# IRLED.net
KiCad netlist of a schematic drawn in Altium Designer
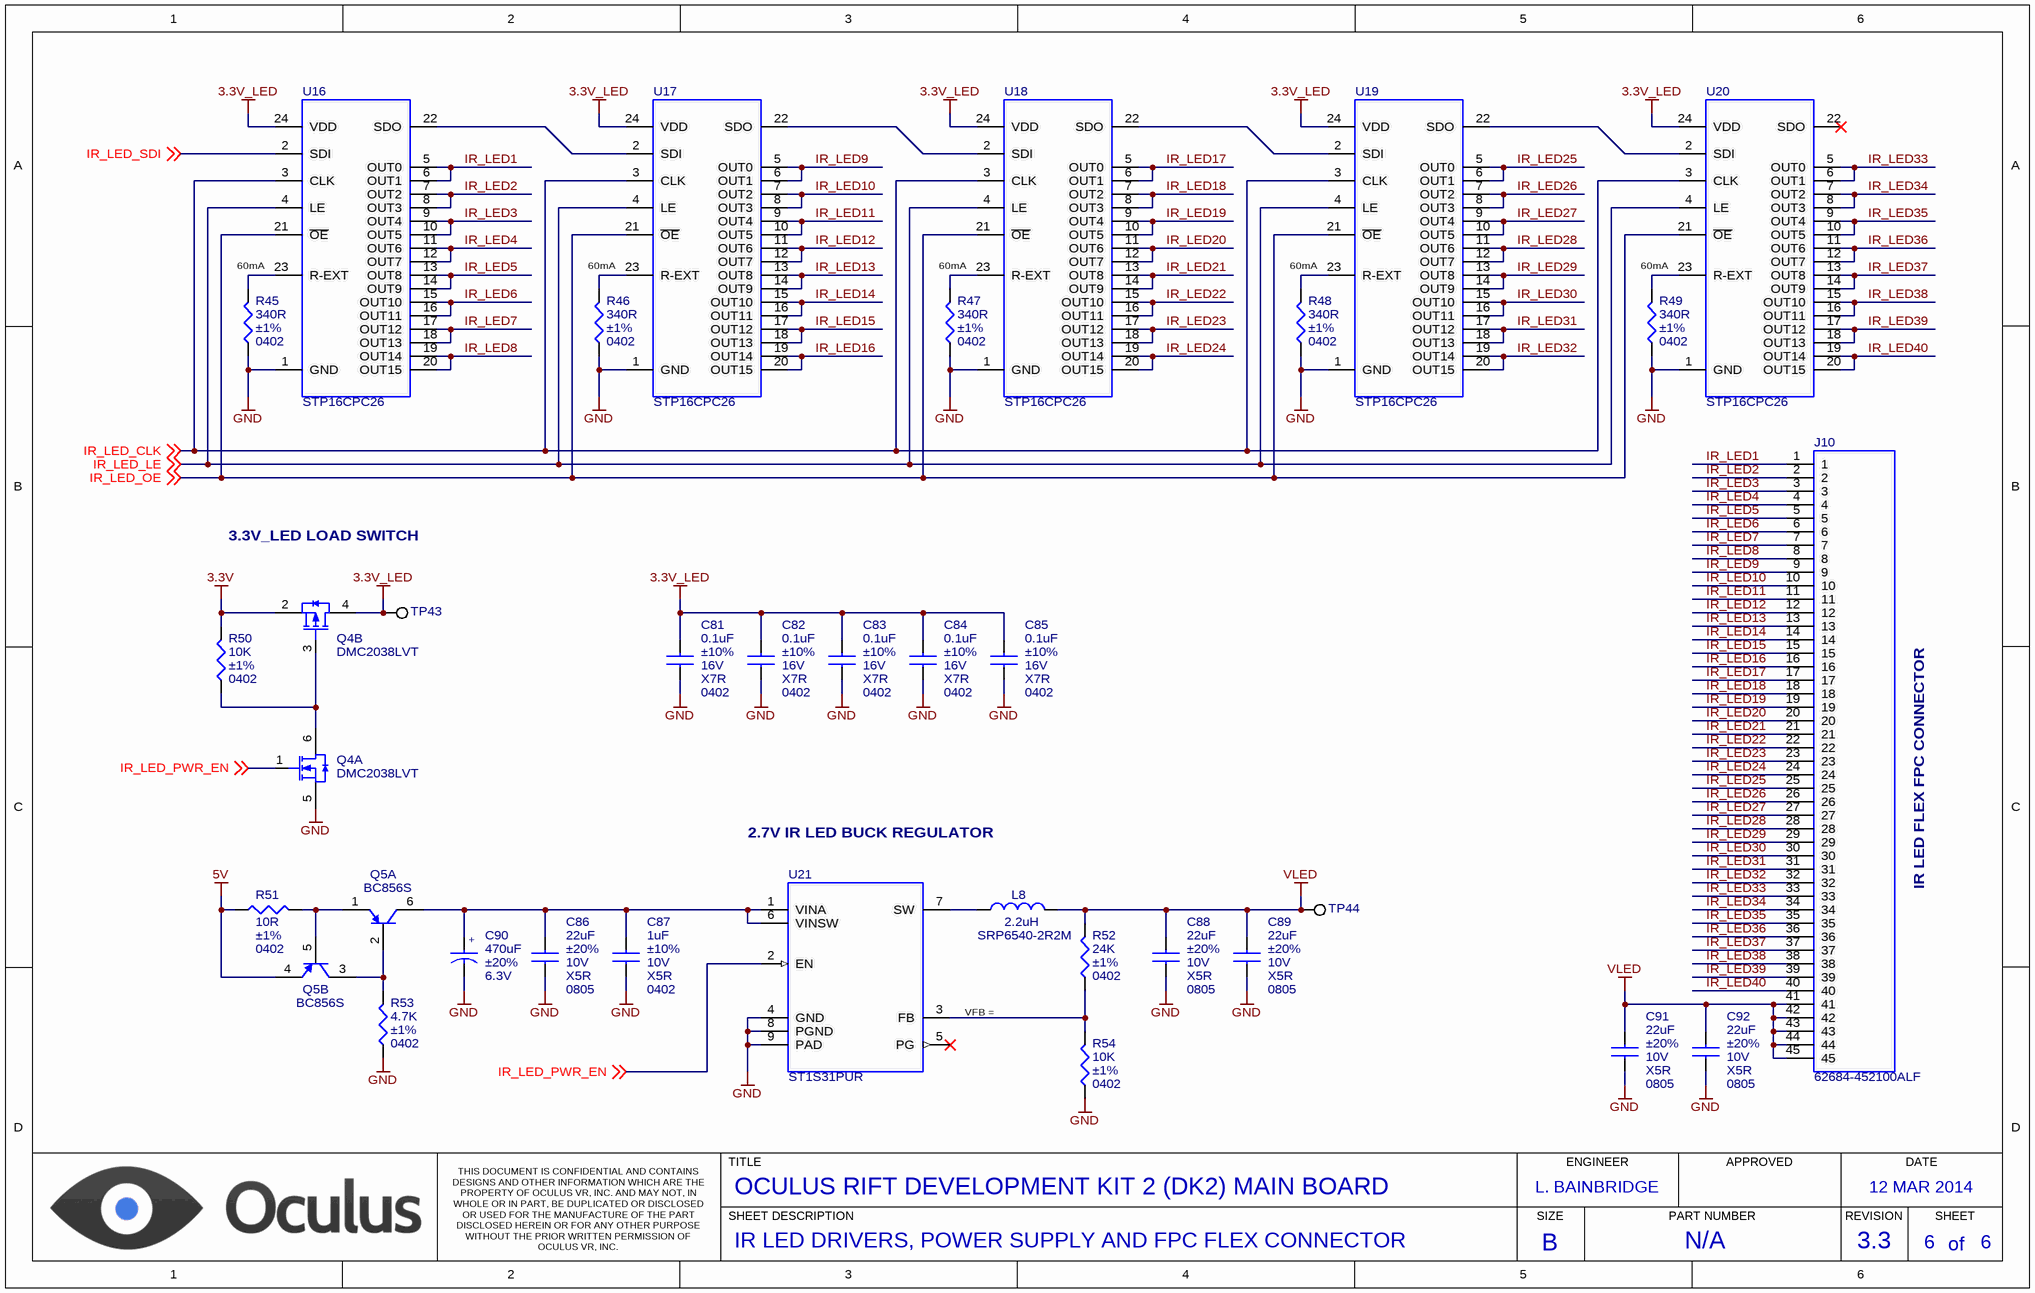
[diagram p0: IRLED.SchDoc]

(export (version "E")
  (design (tool "Eeschema 10.0.6"))
  (components
    (comp (ref "C81")
      (value "0.1uF")
      (footprint "CAP_CERAMIC_0402")
      (description "CAP, CERAMIC, 0.1uF, ±10%, 16V, X7R, 0402")
      (fields
        (field (name "MANUFACTURER") "MURATA ELECTRONICS")
        (field (name "PART NUMBER") "GRM155R71C104KA88D")
        (field (name "TOLERANCE") "±10%")
        (field (name "VOLTAGE") "16V")
        (field (name "DIELECTRIC") "X7R")
        (field (name "PACKAGE") "0402")
      )
      (libsource (lib "DK2") (part "CAP, CERAMIC"))
    )
    (comp (ref "C82")
      (value "0.1uF")
      (footprint "CAP_CERAMIC_0402")
      (description "CAP, CERAMIC, 0.1uF, ±10%, 16V, X7R, 0402")
      (fields
        (field (name "MANUFACTURER") "MURATA ELECTRONICS")
        (field (name "PART NUMBER") "GRM155R71C104KA88D")
        (field (name "TOLERANCE") "±10%")
        (field (name "VOLTAGE") "16V")
        (field (name "DIELECTRIC") "X7R")
        (field (name "PACKAGE") "0402")
      )
      (libsource (lib "DK2") (part "CAP, CERAMIC"))
    )
    (comp (ref "C83")
      (value "0.1uF")
      (footprint "CAP_CERAMIC_0402")
      (description "CAP, CERAMIC, 0.1uF, ±10%, 16V, X7R, 0402")
      (fields
        (field (name "MANUFACTURER") "MURATA ELECTRONICS")
        (field (name "PART NUMBER") "GRM155R71C104KA88D")
        (field (name "TOLERANCE") "±10%")
        (field (name "VOLTAGE") "16V")
        (field (name "DIELECTRIC") "X7R")
        (field (name "PACKAGE") "0402")
      )
      (libsource (lib "DK2") (part "CAP, CERAMIC"))
    )
    (comp (ref "C84")
      (value "0.1uF")
      (footprint "CAP_CERAMIC_0402")
      (description "CAP, CERAMIC, 0.1uF, ±10%, 16V, X7R, 0402")
      (fields
        (field (name "MANUFACTURER") "MURATA ELECTRONICS")
        (field (name "PART NUMBER") "GRM155R71C104KA88D")
        (field (name "TOLERANCE") "±10%")
        (field (name "VOLTAGE") "16V")
        (field (name "DIELECTRIC") "X7R")
        (field (name "PACKAGE") "0402")
      )
      (libsource (lib "DK2") (part "CAP, CERAMIC"))
    )
    (comp (ref "C85")
      (value "0.1uF")
      (footprint "CAP_CERAMIC_0402")
      (description "CAP, CERAMIC, 0.1uF, ±10%, 16V, X7R, 0402")
      (fields
        (field (name "MANUFACTURER") "MURATA ELECTRONICS")
        (field (name "PART NUMBER") "GRM155R71C104KA88D")
        (field (name "TOLERANCE") "±10%")
        (field (name "VOLTAGE") "16V")
        (field (name "DIELECTRIC") "X7R")
        (field (name "PACKAGE") "0402")
      )
      (libsource (lib "DK2") (part "CAP, CERAMIC"))
    )
    (comp (ref "C86")
      (value "22uF")
      (footprint "CAP_CERAMIC_0805")
      (description "CAP, CERAMIC, 22uF, ±20%, 10V, X5R, 0805")
      (fields
        (field (name "MANUFACTURER") "SAMSUNG")
        (field (name "PART NUMBER") "CL21A226MPQNNNE")
        (field (name "TOLERANCE") "±20%")
        (field (name "VOLTAGE") "10V")
        (field (name "DIELECTRIC") "X5R")
        (field (name "PACKAGE") "0805")
      )
      (libsource (lib "DK2") (part "CAP, CERAMIC"))
    )
    (comp (ref "C87")
      (value "1uF")
      (footprint "CAP_CERAMIC_0402")
      (description "CAP, CERAMIC, 1uF, ±10%, 10V, X5R, 0402")
      (fields
        (field (name "MANUFACTURER") "MURATA ELECTRONICS")
        (field (name "PART NUMBER") "GRM155R61A105KE15D")
        (field (name "TOLERANCE") "±10%")
        (field (name "VOLTAGE") "10V")
        (field (name "DIELECTRIC") "X5R")
        (field (name "PACKAGE") "0402")
      )
      (libsource (lib "DK2") (part "CAP, CERAMIC"))
    )
    (comp (ref "C88")
      (value "22uF")
      (footprint "CAP_CERAMIC_0805")
      (description "CAP, CERAMIC, 22uF, ±20%, 10V, X5R, 0805")
      (fields
        (field (name "MANUFACTURER") "SAMSUNG")
        (field (name "PART NUMBER") "CL21A226MPQNNNE")
        (field (name "TOLERANCE") "±20%")
        (field (name "VOLTAGE") "10V")
        (field (name "DIELECTRIC") "X5R")
        (field (name "PACKAGE") "0805")
      )
      (libsource (lib "DK2") (part "CAP, CERAMIC"))
    )
    (comp (ref "C89")
      (value "22uF")
      (footprint "CAP_CERAMIC_0805")
      (description "CAP, CERAMIC, 22uF, ±20%, 10V, X5R, 0805")
      (fields
        (field (name "MANUFACTURER") "SAMSUNG")
        (field (name "PART NUMBER") "CL21A226MPQNNNE")
        (field (name "TOLERANCE") "±20%")
        (field (name "VOLTAGE") "10V")
        (field (name "DIELECTRIC") "X5R")
        (field (name "PACKAGE") "0805")
      )
      (libsource (lib "DK2") (part "CAP, CERAMIC"))
    )
    (comp (ref "C90")
      (value "470uF")
      (footprint "7343-38")
      (description "CAP, TANTALUM, 470uF, ±20%, 6.3V, 7343-38")
      (fields
        (field (name "MANUFACTURER") "PANASONIC")
        (field (name "PART NUMBER") "6TPB470M")
        (field (name "VOLTAGE") "6.3V")
        (field (name "TOLERANCE") "±20%")
      )
      (libsource (lib "DK2") (part "CAP, TANTALUM"))
    )
    (comp (ref "C91")
      (value "22uF")
      (footprint "CAP_CERAMIC_0805")
      (description "CAP, CERAMIC, 22uF, ±20%, 10V, X5R, 0805")
      (fields
        (field (name "MANUFACTURER") "SAMSUNG")
        (field (name "PART NUMBER") "CL21A226MPQNNNE")
        (field (name "TOLERANCE") "±20%")
        (field (name "VOLTAGE") "10V")
        (field (name "DIELECTRIC") "X5R")
        (field (name "PACKAGE") "0805")
      )
      (libsource (lib "DK2") (part "CAP, CERAMIC"))
    )
    (comp (ref "C92")
      (value "22uF")
      (footprint "CAP_CERAMIC_0805")
      (description "CAP, CERAMIC, 22uF, ±20%, 10V, X5R, 0805")
      (fields
        (field (name "MANUFACTURER") "SAMSUNG")
        (field (name "PART NUMBER") "CL21A226MPQNNNE")
        (field (name "TOLERANCE") "±20%")
        (field (name "VOLTAGE") "10V")
        (field (name "DIELECTRIC") "X5R")
        (field (name "PACKAGE") "0805")
      )
      (libsource (lib "DK2") (part "CAP, CERAMIC"))
    )
    (comp (ref "J10")
      (value "62684-452100ALF")
      (footprint "FCI_62684-452100ALF")
      (description "CONNECTOR, FPC HEADER, 45 POS, 0.5MM PITCH")
      (fields (field (name "MANUFACTURER") "FCI"))
      (libsource (lib "DK2") (part "62684-452100ALF"))
    )
    (comp (ref "L8")
      (value "2.2uH")
      (footprint "SRP6540")
      (description "INDUCTOR, SHIELDED POWER, 2.2uH, 9A")
      (fields (field (name "MANUFACTURER") "BOURNES") (field (name "PART NUMBER") "SRP6540-2R2M"))
      (libsource (lib "DK2") (part "INDUCTOR"))
    )
    (comp (ref "Q4")
      (value "DMC2038LVT")
      (footprint "TSOT26")
      (description "FET, COMPLEMENTARY, LOGIC LEVEL")
      (fields (field (name "MANUFACTURER") "DIODES INC"))
      (libsource (lib "DK2") (part "DMC2038LVT"))
    )
    (comp (ref "Q5")
      (value "BC856S")
      (footprint "SOT363")
      (description "TRANSISTOR, DUAL SILICON PNP")
      (fields (field (name "MANUFACTURER") "INFINEON") (field (name "PART NUMBER") "BC856S H6327"))
      (libsource (lib "DK2") (part "BC856S"))
    )
    (comp (ref "R45")
      (value "340R")
      (footprint "RESISTOR_0402")
      (description "RES 340 OHM, 1/10W, ±1%, 0402")
      (fields
        (field (name "MANUFACTURER") "PANASONIC")
        (field (name "PART NUMBER") "ERJ-2RKF3400X")
        (field (name "PACKAGE") "0402")
        (field (name "TOLERANCE") "±1%")
      )
      (libsource (lib "DK2") (part "RESISTOR"))
    )
    (comp (ref "R46")
      (value "340R")
      (footprint "RESISTOR_0402")
      (description "RES 340 OHM, 1/10W, ±1%, 0402")
      (fields
        (field (name "MANUFACTURER") "PANASONIC")
        (field (name "PART NUMBER") "ERJ-2RKF3400X")
        (field (name "PACKAGE") "0402")
        (field (name "TOLERANCE") "±1%")
      )
      (libsource (lib "DK2") (part "RESISTOR"))
    )
    (comp (ref "R47")
      (value "340R")
      (footprint "RESISTOR_0402")
      (description "RES 340 OHM, 1/10W, ±1%, 0402")
      (fields
        (field (name "MANUFACTURER") "PANASONIC")
        (field (name "PART NUMBER") "ERJ-2RKF3400X")
        (field (name "PACKAGE") "0402")
        (field (name "TOLERANCE") "±1%")
      )
      (libsource (lib "DK2") (part "RESISTOR"))
    )
    (comp (ref "R48")
      (value "340R")
      (footprint "RESISTOR_0402")
      (description "RES 340 OHM, 1/10W, ±1%, 0402")
      (fields
        (field (name "MANUFACTURER") "PANASONIC")
        (field (name "PART NUMBER") "ERJ-2RKF3400X")
        (field (name "PACKAGE") "0402")
        (field (name "TOLERANCE") "±1%")
      )
      (libsource (lib "DK2") (part "RESISTOR"))
    )
    (comp (ref "R49")
      (value "340R")
      (footprint "RESISTOR_0402")
      (description "RES 340 OHM, 1/10W, ±1%, 0402")
      (fields
        (field (name "MANUFACTURER") "PANASONIC")
        (field (name "PART NUMBER") "ERJ-2RKF3400X")
        (field (name "PACKAGE") "0402")
        (field (name "TOLERANCE") "±1%")
      )
      (libsource (lib "DK2") (part "RESISTOR"))
    )
    (comp (ref "R50")
      (value "10K")
      (footprint "RESISTOR_0402")
      (description "RES, 10K OHM, 1/10W, ±1%, 0402")
      (fields
        (field (name "MANUFACTURER") "PANASONIC")
        (field (name "PART NUMBER") "ERJ-2RKF1002X")
        (field (name "PACKAGE") "0402")
        (field (name "TOLERANCE") "±1%")
      )
      (libsource (lib "DK2") (part "RESISTOR"))
    )
    (comp (ref "R51")
      (value "10R")
      (footprint "RESISTOR_0402")
      (description "RES, 10 OHM, 1/10W, ±1%, 0402")
      (fields
        (field (name "MANUFACTURER") "PANASONIC")
        (field (name "PART NUMBER") "ERJ-2RKF10R0X")
        (field (name "PACKAGE") "0402")
        (field (name "TOLERANCE") "±1%")
      )
      (libsource (lib "DK2") (part "RESISTOR"))
    )
    (comp (ref "R52")
      (value "24K")
      (footprint "RESISTOR_0402")
      (description "RES, 24K OHM, 1/10W, ±1%, 0402")
      (fields
        (field (name "MANUFACTURER") "PANASONIC")
        (field (name "PART NUMBER") "ERJ-2RKF2402X")
        (field (name "PACKAGE") "0402")
        (field (name "TOLERANCE") "±1%")
      )
      (libsource (lib "DK2") (part "RESISTOR"))
    )
    (comp (ref "R53")
      (value "4.7K")
      (footprint "RESISTOR_0402")
      (description "RES, 4.7K OHM, 1/10W, ±1%, 0402")
      (fields
        (field (name "MANUFACTURER") "PANASONIC")
        (field (name "PART NUMBER") "ERJ-2RKF4701X")
        (field (name "PACKAGE") "0402")
        (field (name "TOLERANCE") "±1%")
      )
      (libsource (lib "DK2") (part "RESISTOR"))
    )
    (comp (ref "R54")
      (value "10K")
      (footprint "RESISTOR_0402")
      (description "RES, 10K OHM, 1/10W, ±1%, 0402")
      (fields
        (field (name "MANUFACTURER") "PANASONIC")
        (field (name "PART NUMBER") "ERJ-2RKF1002X")
        (field (name "PACKAGE") "0402")
        (field (name "TOLERANCE") "±1%")
      )
      (libsource (lib "DK2") (part "RESISTOR"))
    )
    (comp (ref "TP43")
      (value "TEST POINT")
      (footprint "TEST_POINT_PAD_1MM")
      (libsource (lib "DK2") (part "TEST_POINT_GENERIC"))
    )
    (comp (ref "TP44")
      (value "TEST POINT")
      (footprint "TEST_POINT_PAD_1MM")
      (libsource (lib "DK2") (part "TEST_POINT_GENERIC"))
    )
    (comp (ref "U16")
      (value "STP16CPC26")
      (footprint "TSSOP24")
      (description "IC, LED DRIVER, 16-BIT CONSTANT CURRENT SINK DRIVER")
      (fields (field (name "MANUFACTURER") "STMICROELECTRONICS") (field (name "PART NUMBER") "STP16CPC26TTR"))
      (libsource (lib "DK2") (part "STP16CPC26"))
    )
    (comp (ref "U17")
      (value "STP16CPC26")
      (footprint "TSSOP24")
      (description "IC, LED DRIVER, 16-BIT CONSTANT CURRENT SINK DRIVER")
      (fields (field (name "MANUFACTURER") "STMICROELECTRONICS") (field (name "PART NUMBER") "STP16CPC26TTR"))
      (libsource (lib "DK2") (part "STP16CPC26"))
    )
    (comp (ref "U18")
      (value "STP16CPC26")
      (footprint "TSSOP24")
      (description "IC, LED DRIVER, 16-BIT CONSTANT CURRENT SINK DRIVER")
      (fields (field (name "MANUFACTURER") "STMICROELECTRONICS") (field (name "PART NUMBER") "STP16CPC26TTR"))
      (libsource (lib "DK2") (part "STP16CPC26"))
    )
    (comp (ref "U19")
      (value "STP16CPC26")
      (footprint "TSSOP24")
      (description "IC, LED DRIVER, 16-BIT CONSTANT CURRENT SINK DRIVER")
      (fields (field (name "MANUFACTURER") "STMICROELECTRONICS") (field (name "PART NUMBER") "STP16CPC26TTR"))
      (libsource (lib "DK2") (part "STP16CPC26"))
    )
    (comp (ref "U20")
      (value "STP16CPC26")
      (footprint "TSSOP24")
      (description "IC, LED DRIVER, 16-BIT CONSTANT CURRENT SINK DRIVER")
      (fields (field (name "MANUFACTURER") "STMICROELECTRONICS") (field (name "PART NUMBER") "STP16CPC26TTR"))
      (libsource (lib "DK2") (part "STP16CPC26"))
    )
    (comp (ref "U21")
      (value "ST1S31PUR")
      (footprint "VFDFPN-3x3-8L")
      (description "IC, BUCK REGULATOR, 3A")
      (fields (field (name "MANUFACTURER") "STMICROELECTRONICS"))
      (libsource (lib "DK2") (part "ST1S31PUR"))
    )
  )
  (nets
    (net (code "1") (name "/IR_LED1") (class "Default")
      (node (ref "J10") (pin "1") (pinfunction "1_1") (pintype "passive"))
      (node (ref "U16") (pin "5") (pinfunction "OUT0_5") (pintype "passive"))
      (node (ref "U16") (pin "6") (pinfunction "OUT1_6") (pintype "passive"))
    )
    (net (code "2") (name "/IR_LED2") (class "Default")
      (node (ref "J10") (pin "2") (pinfunction "2_2") (pintype "passive"))
      (node (ref "U16") (pin "7") (pinfunction "OUT2_7") (pintype "passive"))
      (node (ref "U16") (pin "8") (pinfunction "OUT3_8") (pintype "passive"))
    )
    (net (code "3") (name "/IR_LED3") (class "Default")
      (node (ref "J10") (pin "3") (pinfunction "3_3") (pintype "passive"))
      (node (ref "U16") (pin "10") (pinfunction "OUT5_10") (pintype "passive"))
      (node (ref "U16") (pin "9") (pinfunction "OUT4_9") (pintype "passive"))
    )
    (net (code "4") (name "/IR_LED4") (class "Default")
      (node (ref "J10") (pin "4") (pinfunction "4_4") (pintype "passive"))
      (node (ref "U16") (pin "11") (pinfunction "OUT6_11") (pintype "passive"))
      (node (ref "U16") (pin "12") (pinfunction "OUT7_12") (pintype "passive"))
    )
    (net (code "5") (name "/IR_LED5") (class "Default")
      (node (ref "J10") (pin "5") (pinfunction "5_5") (pintype "passive"))
      (node (ref "U16") (pin "13") (pinfunction "OUT8_13") (pintype "passive"))
      (node (ref "U16") (pin "14") (pinfunction "OUT9_14") (pintype "passive"))
    )
    (net (code "6") (name "/IR_LED6") (class "Default")
      (node (ref "J10") (pin "6") (pinfunction "6_6") (pintype "passive"))
      (node (ref "U16") (pin "15") (pinfunction "OUT10_15") (pintype "passive"))
      (node (ref "U16") (pin "16") (pinfunction "OUT11_16") (pintype "passive"))
    )
    (net (code "7") (name "/IR_LED7") (class "Default")
      (node (ref "J10") (pin "7") (pinfunction "7_7") (pintype "passive"))
      (node (ref "U16") (pin "17") (pinfunction "OUT12_17") (pintype "passive"))
      (node (ref "U16") (pin "18") (pinfunction "OUT13_18") (pintype "passive"))
    )
    (net (code "8") (name "/IR_LED8") (class "Default")
      (node (ref "J10") (pin "8") (pinfunction "8_8") (pintype "passive"))
      (node (ref "U16") (pin "19") (pinfunction "OUT14_19") (pintype "passive"))
      (node (ref "U16") (pin "20") (pinfunction "OUT15_20") (pintype "passive"))
    )
    (net (code "9") (name "/IR_LED9") (class "Default")
      (node (ref "J10") (pin "9") (pinfunction "9_9") (pintype "passive"))
      (node (ref "U17") (pin "5") (pinfunction "OUT0_5") (pintype "passive"))
      (node (ref "U17") (pin "6") (pinfunction "OUT1_6") (pintype "passive"))
    )
    (net (code "10") (name "/IR_LED10") (class "Default")
      (node (ref "J10") (pin "10") (pinfunction "10_10") (pintype "passive"))
      (node (ref "U17") (pin "7") (pinfunction "OUT2_7") (pintype "passive"))
      (node (ref "U17") (pin "8") (pinfunction "OUT3_8") (pintype "passive"))
    )
    (net (code "11") (name "/IR_LED11") (class "Default")
      (node (ref "J10") (pin "11") (pinfunction "11_11") (pintype "passive"))
      (node (ref "U17") (pin "10") (pinfunction "OUT5_10") (pintype "passive"))
      (node (ref "U17") (pin "9") (pinfunction "OUT4_9") (pintype "passive"))
    )
    (net (code "12") (name "/IR_LED12") (class "Default")
      (node (ref "J10") (pin "12") (pinfunction "12_12") (pintype "passive"))
      (node (ref "U17") (pin "11") (pinfunction "OUT6_11") (pintype "passive"))
      (node (ref "U17") (pin "12") (pinfunction "OUT7_12") (pintype "passive"))
    )
    (net (code "13") (name "/IR_LED13") (class "Default")
      (node (ref "J10") (pin "13") (pinfunction "13_13") (pintype "passive"))
      (node (ref "U17") (pin "13") (pinfunction "OUT8_13") (pintype "passive"))
      (node (ref "U17") (pin "14") (pinfunction "OUT9_14") (pintype "passive"))
    )
    (net (code "14") (name "/IR_LED14") (class "Default")
      (node (ref "J10") (pin "14") (pinfunction "14_14") (pintype "passive"))
      (node (ref "U17") (pin "15") (pinfunction "OUT10_15") (pintype "passive"))
      (node (ref "U17") (pin "16") (pinfunction "OUT11_16") (pintype "passive"))
    )
    (net (code "15") (name "/IR_LED15") (class "Default")
      (node (ref "J10") (pin "15") (pinfunction "15_15") (pintype "passive"))
      (node (ref "U17") (pin "17") (pinfunction "OUT12_17") (pintype "passive"))
      (node (ref "U17") (pin "18") (pinfunction "OUT13_18") (pintype "passive"))
    )
    (net (code "16") (name "/IR_LED16") (class "Default")
      (node (ref "J10") (pin "16") (pinfunction "16_16") (pintype "passive"))
      (node (ref "U17") (pin "19") (pinfunction "OUT14_19") (pintype "passive"))
      (node (ref "U17") (pin "20") (pinfunction "OUT15_20") (pintype "passive"))
    )
    (net (code "17") (name "/IR_LED17") (class "Default")
      (node (ref "J10") (pin "17") (pinfunction "17_17") (pintype "passive"))
      (node (ref "U18") (pin "5") (pinfunction "OUT0_5") (pintype "passive"))
      (node (ref "U18") (pin "6") (pinfunction "OUT1_6") (pintype "passive"))
    )
    (net (code "18") (name "/IR_LED18") (class "Default")
      (node (ref "J10") (pin "18") (pinfunction "18_18") (pintype "passive"))
      (node (ref "U18") (pin "7") (pinfunction "OUT2_7") (pintype "passive"))
      (node (ref "U18") (pin "8") (pinfunction "OUT3_8") (pintype "passive"))
    )
    (net (code "19") (name "/IR_LED19") (class "Default")
      (node (ref "J10") (pin "19") (pinfunction "19_19") (pintype "passive"))
      (node (ref "U18") (pin "10") (pinfunction "OUT5_10") (pintype "passive"))
      (node (ref "U18") (pin "9") (pinfunction "OUT4_9") (pintype "passive"))
    )
    (net (code "20") (name "/IR_LED20") (class "Default")
      (node (ref "J10") (pin "20") (pinfunction "20_20") (pintype "passive"))
      (node (ref "U18") (pin "11") (pinfunction "OUT6_11") (pintype "passive"))
      (node (ref "U18") (pin "12") (pinfunction "OUT7_12") (pintype "passive"))
    )
    (net (code "21") (name "/IR_LED21") (class "Default")
      (node (ref "J10") (pin "21") (pinfunction "21_21") (pintype "passive"))
      (node (ref "U18") (pin "13") (pinfunction "OUT8_13") (pintype "passive"))
      (node (ref "U18") (pin "14") (pinfunction "OUT9_14") (pintype "passive"))
    )
    (net (code "22") (name "/IR_LED22") (class "Default")
      (node (ref "J10") (pin "22") (pinfunction "22_22") (pintype "passive"))
      (node (ref "U18") (pin "15") (pinfunction "OUT10_15") (pintype "passive"))
      (node (ref "U18") (pin "16") (pinfunction "OUT11_16") (pintype "passive"))
    )
    (net (code "23") (name "/IR_LED23") (class "Default")
      (node (ref "J10") (pin "23") (pinfunction "23_23") (pintype "passive"))
      (node (ref "U18") (pin "17") (pinfunction "OUT12_17") (pintype "passive"))
      (node (ref "U18") (pin "18") (pinfunction "OUT13_18") (pintype "passive"))
    )
    (net (code "24") (name "/IR_LED24") (class "Default")
      (node (ref "J10") (pin "24") (pinfunction "24_24") (pintype "passive"))
      (node (ref "U18") (pin "19") (pinfunction "OUT14_19") (pintype "passive"))
      (node (ref "U18") (pin "20") (pinfunction "OUT15_20") (pintype "passive"))
    )
    (net (code "25") (name "/IR_LED25") (class "Default")
      (node (ref "J10") (pin "25") (pinfunction "25_25") (pintype "passive"))
      (node (ref "U19") (pin "5") (pinfunction "OUT0_5") (pintype "passive"))
      (node (ref "U19") (pin "6") (pinfunction "OUT1_6") (pintype "passive"))
    )
    (net (code "26") (name "/IR_LED26") (class "Default")
      (node (ref "J10") (pin "26") (pinfunction "26_26") (pintype "passive"))
      (node (ref "U19") (pin "7") (pinfunction "OUT2_7") (pintype "passive"))
      (node (ref "U19") (pin "8") (pinfunction "OUT3_8") (pintype "passive"))
    )
    (net (code "27") (name "/IR_LED27") (class "Default")
      (node (ref "J10") (pin "27") (pinfunction "27_27") (pintype "passive"))
      (node (ref "U19") (pin "10") (pinfunction "OUT5_10") (pintype "passive"))
      (node (ref "U19") (pin "9") (pinfunction "OUT4_9") (pintype "passive"))
    )
    (net (code "28") (name "/IR_LED28") (class "Default")
      (node (ref "J10") (pin "28") (pinfunction "28_28") (pintype "passive"))
      (node (ref "U19") (pin "11") (pinfunction "OUT6_11") (pintype "passive"))
      (node (ref "U19") (pin "12") (pinfunction "OUT7_12") (pintype "passive"))
    )
    (net (code "29") (name "/IR_LED29") (class "Default")
      (node (ref "J10") (pin "29") (pinfunction "29_29") (pintype "passive"))
      (node (ref "U19") (pin "13") (pinfunction "OUT8_13") (pintype "passive"))
      (node (ref "U19") (pin "14") (pinfunction "OUT9_14") (pintype "passive"))
    )
    (net (code "30") (name "/IR_LED30") (class "Default")
      (node (ref "J10") (pin "30") (pinfunction "30_30") (pintype "passive"))
      (node (ref "U19") (pin "15") (pinfunction "OUT10_15") (pintype "passive"))
      (node (ref "U19") (pin "16") (pinfunction "OUT11_16") (pintype "passive"))
    )
    (net (code "31") (name "/IR_LED31") (class "Default")
      (node (ref "J10") (pin "31") (pinfunction "31_31") (pintype "passive"))
      (node (ref "U19") (pin "17") (pinfunction "OUT12_17") (pintype "passive"))
      (node (ref "U19") (pin "18") (pinfunction "OUT13_18") (pintype "passive"))
    )
    (net (code "32") (name "/IR_LED32") (class "Default")
      (node (ref "J10") (pin "32") (pinfunction "32_32") (pintype "passive"))
      (node (ref "U19") (pin "19") (pinfunction "OUT14_19") (pintype "passive"))
      (node (ref "U19") (pin "20") (pinfunction "OUT15_20") (pintype "passive"))
    )
    (net (code "33") (name "/IR_LED33") (class "Default")
      (node (ref "J10") (pin "33") (pinfunction "33_33") (pintype "passive"))
      (node (ref "U20") (pin "5") (pinfunction "OUT0_5") (pintype "passive"))
      (node (ref "U20") (pin "6") (pinfunction "OUT1_6") (pintype "passive"))
    )
    (net (code "34") (name "/IR_LED34") (class "Default")
      (node (ref "J10") (pin "34") (pinfunction "34_34") (pintype "passive"))
      (node (ref "U20") (pin "7") (pinfunction "OUT2_7") (pintype "passive"))
      (node (ref "U20") (pin "8") (pinfunction "OUT3_8") (pintype "passive"))
    )
    (net (code "35") (name "/IR_LED35") (class "Default")
      (node (ref "J10") (pin "35") (pinfunction "35_35") (pintype "passive"))
      (node (ref "U20") (pin "10") (pinfunction "OUT5_10") (pintype "passive"))
      (node (ref "U20") (pin "9") (pinfunction "OUT4_9") (pintype "passive"))
    )
    (net (code "36") (name "/IR_LED36") (class "Default")
      (node (ref "J10") (pin "36") (pinfunction "36_36") (pintype "passive"))
      (node (ref "U20") (pin "11") (pinfunction "OUT6_11") (pintype "passive"))
      (node (ref "U20") (pin "12") (pinfunction "OUT7_12") (pintype "passive"))
    )
    (net (code "37") (name "/IR_LED37") (class "Default")
      (node (ref "J10") (pin "37") (pinfunction "37_37") (pintype "passive"))
      (node (ref "U20") (pin "13") (pinfunction "OUT8_13") (pintype "passive"))
      (node (ref "U20") (pin "14") (pinfunction "OUT9_14") (pintype "passive"))
    )
    (net (code "38") (name "/IR_LED38") (class "Default")
      (node (ref "J10") (pin "38") (pinfunction "38_38") (pintype "passive"))
      (node (ref "U20") (pin "15") (pinfunction "OUT10_15") (pintype "passive"))
      (node (ref "U20") (pin "16") (pinfunction "OUT11_16") (pintype "passive"))
    )
    (net (code "39") (name "/IR_LED39") (class "Default")
      (node (ref "J10") (pin "39") (pinfunction "39_39") (pintype "passive"))
      (node (ref "U20") (pin "17") (pinfunction "OUT12_17") (pintype "passive"))
      (node (ref "U20") (pin "18") (pinfunction "OUT13_18") (pintype "passive"))
    )
    (net (code "40") (name "/IR_LED40") (class "Default")
      (node (ref "J10") (pin "40") (pinfunction "40_40") (pintype "passive"))
      (node (ref "U20") (pin "19") (pinfunction "OUT14_19") (pintype "passive"))
      (node (ref "U20") (pin "20") (pinfunction "OUT15_20") (pintype "passive"))
    )
    (net (code "41") (name "3.3V") (class "Default")
      (node (ref "Q4") (pin "2") (pinfunction "S_2") (pintype "passive"))
      (node (ref "R50") (pin "2") (pinfunction "2_2") (pintype "passive"))
    )
    (net (code "42") (name "3.3V_LED") (class "Default")
      (node (ref "C81") (pin "1") (pinfunction "1_1") (pintype "passive"))
      (node (ref "C82") (pin "1") (pinfunction "1_1") (pintype "passive"))
      (node (ref "C83") (pin "1") (pinfunction "1_1") (pintype "passive"))
      (node (ref "C84") (pin "1") (pinfunction "1_1") (pintype "passive"))
      (node (ref "C85") (pin "1") (pinfunction "1_1") (pintype "passive"))
      (node (ref "Q4") (pin "4") (pinfunction "D_4") (pintype "passive"))
      (node (ref "TP43") (pin "1") (pinfunction "1_1") (pintype "passive"))
      (node (ref "U16") (pin "24") (pinfunction "VDD_24") (pintype "passive"))
      (node (ref "U17") (pin "24") (pinfunction "VDD_24") (pintype "passive"))
      (node (ref "U18") (pin "24") (pinfunction "VDD_24") (pintype "passive"))
      (node (ref "U19") (pin "24") (pinfunction "VDD_24") (pintype "passive"))
      (node (ref "U20") (pin "24") (pinfunction "VDD_24") (pintype "passive"))
    )
    (net (code "43") (name "5V") (class "Default")
      (node (ref "Q5") (pin "4") (pinfunction "E_4") (pintype "passive"))
      (node (ref "R51") (pin "1") (pinfunction "1_1") (pintype "passive"))
    )
    (net (code "44") (name "GND") (class "Default")
      (node (ref "C81") (pin "2") (pinfunction "2_2") (pintype "passive"))
      (node (ref "C82") (pin "2") (pinfunction "2_2") (pintype "passive"))
      (node (ref "C83") (pin "2") (pinfunction "2_2") (pintype "passive"))
      (node (ref "C84") (pin "2") (pinfunction "2_2") (pintype "passive"))
      (node (ref "C85") (pin "2") (pinfunction "2_2") (pintype "passive"))
      (node (ref "C86") (pin "2") (pinfunction "2_2") (pintype "passive"))
      (node (ref "C87") (pin "2") (pinfunction "2_2") (pintype "passive"))
      (node (ref "C88") (pin "2") (pinfunction "2_2") (pintype "passive"))
      (node (ref "C89") (pin "2") (pinfunction "2_2") (pintype "passive"))
      (node (ref "C90") (pin "2") (pinfunction "2_2") (pintype "passive"))
      (node (ref "C91") (pin "2") (pinfunction "2_2") (pintype "passive"))
      (node (ref "C92") (pin "2") (pinfunction "2_2") (pintype "passive"))
      (node (ref "Q4") (pin "5") (pinfunction "S_5") (pintype "passive"))
      (node (ref "R45") (pin "1") (pinfunction "1_1") (pintype "passive"))
      (node (ref "R46") (pin "1") (pinfunction "1_1") (pintype "passive"))
      (node (ref "R47") (pin "1") (pinfunction "1_1") (pintype "passive"))
      (node (ref "R48") (pin "1") (pinfunction "1_1") (pintype "passive"))
      (node (ref "R49") (pin "1") (pinfunction "1_1") (pintype "passive"))
      (node (ref "R53") (pin "1") (pinfunction "1_1") (pintype "passive"))
      (node (ref "R54") (pin "1") (pinfunction "1_1") (pintype "passive"))
      (node (ref "U16") (pin "1") (pinfunction "GND_1") (pintype "passive"))
      (node (ref "U17") (pin "1") (pinfunction "GND_1") (pintype "passive"))
      (node (ref "U18") (pin "1") (pinfunction "GND_1") (pintype "passive"))
      (node (ref "U19") (pin "1") (pinfunction "GND_1") (pintype "passive"))
      (node (ref "U20") (pin "1") (pinfunction "GND_1") (pintype "passive"))
      (node (ref "U21") (pin "4") (pinfunction "GND_4") (pintype "power_in"))
      (node (ref "U21") (pin "8") (pinfunction "PGND_8") (pintype "power_in"))
      (node (ref "U21") (pin "9") (pinfunction "PAD_9") (pintype "passive"))
    )
    (net (code "45") (name "IR_LED_CLK") (class "Default")
      (node (ref "U16") (pin "3") (pinfunction "CLK_3") (pintype "passive"))
      (node (ref "U17") (pin "3") (pinfunction "CLK_3") (pintype "passive"))
      (node (ref "U18") (pin "3") (pinfunction "CLK_3") (pintype "passive"))
      (node (ref "U19") (pin "3") (pinfunction "CLK_3") (pintype "passive"))
      (node (ref "U20") (pin "3") (pinfunction "CLK_3") (pintype "passive"))
    )
    (net (code "46") (name "IR_LED_LE") (class "Default")
      (node (ref "U16") (pin "4") (pinfunction "LE_4") (pintype "passive"))
      (node (ref "U17") (pin "4") (pinfunction "LE_4") (pintype "passive"))
      (node (ref "U18") (pin "4") (pinfunction "LE_4") (pintype "passive"))
      (node (ref "U19") (pin "4") (pinfunction "LE_4") (pintype "passive"))
      (node (ref "U20") (pin "4") (pinfunction "LE_4") (pintype "passive"))
    )
    (net (code "47") (name "IR_LED_OE") (class "Default")
      (node (ref "U16") (pin "21") (pinfunction "~{OE}_21") (pintype "passive"))
      (node (ref "U17") (pin "21") (pinfunction "~{OE}_21") (pintype "passive"))
      (node (ref "U18") (pin "21") (pinfunction "~{OE}_21") (pintype "passive"))
      (node (ref "U19") (pin "21") (pinfunction "~{OE}_21") (pintype "passive"))
      (node (ref "U20") (pin "21") (pinfunction "~{OE}_21") (pintype "passive"))
    )
    (net (code "48") (name "IR_LED_PWR_EN") (class "Default")
      (node (ref "Q4") (pin "1") (pinfunction "G_1") (pintype "passive"))
      (node (ref "U21") (pin "2") (pinfunction "EN_2") (pintype "input"))
    )
    (net (code "49") (name "IR_LED_SDI") (class "Default")
      (node (ref "U16") (pin "2") (pinfunction "SDI_2") (pintype "passive"))
    )
    (net (code "50") (name "Net-(Q4A-D)") (class "Default")
      (node (ref "Q4") (pin "3") (pinfunction "G_3") (pintype "passive"))
      (node (ref "Q4") (pin "6") (pinfunction "D_6") (pintype "passive"))
      (node (ref "R50") (pin "1") (pinfunction "1_1") (pintype "passive"))
    )
    (net (code "51") (name "Net-(Q5A-B)") (class "Default")
      (node (ref "Q5") (pin "2") (pinfunction "B_2") (pintype "passive"))
      (node (ref "Q5") (pin "3") (pinfunction "C_3") (pintype "passive"))
      (node (ref "R53") (pin "2") (pinfunction "2_2") (pintype "passive"))
    )
    (net (code "52") (name "Net-(Q5A-C)") (class "Default")
      (node (ref "C86") (pin "1") (pinfunction "1_1") (pintype "passive"))
      (node (ref "C87") (pin "1") (pinfunction "1_1") (pintype "passive"))
      (node (ref "C90") (pin "1") (pinfunction "1_1") (pintype "passive"))
      (node (ref "Q5") (pin "6") (pinfunction "C_6") (pintype "passive"))
      (node (ref "U21") (pin "1") (pinfunction "VINA_1") (pintype "power_in"))
      (node (ref "U21") (pin "6") (pinfunction "VINSW_6") (pintype "power_in"))
    )
    (net (code "53") (name "Net-(Q5A-E)") (class "Default")
      (node (ref "Q5") (pin "1") (pinfunction "E_1") (pintype "passive"))
      (node (ref "Q5") (pin "5") (pinfunction "B_5") (pintype "passive"))
      (node (ref "R51") (pin "2") (pinfunction "2_2") (pintype "passive"))
    )
    (net (code "54") (name "Net-(U16-R-EXT)") (class "Default")
      (node (ref "R45") (pin "2") (pinfunction "2_2") (pintype "passive"))
      (node (ref "U16") (pin "23") (pinfunction "R-EXT_23") (pintype "passive"))
    )
    (net (code "55") (name "Net-(U16-SDO)") (class "Default")
      (node (ref "U16") (pin "22") (pinfunction "SDO_22") (pintype "passive"))
      (node (ref "U17") (pin "2") (pinfunction "SDI_2") (pintype "passive"))
    )
    (net (code "56") (name "Net-(U17-R-EXT)") (class "Default")
      (node (ref "R46") (pin "2") (pinfunction "2_2") (pintype "passive"))
      (node (ref "U17") (pin "23") (pinfunction "R-EXT_23") (pintype "passive"))
    )
    (net (code "57") (name "Net-(U17-SDO)") (class "Default")
      (node (ref "U17") (pin "22") (pinfunction "SDO_22") (pintype "passive"))
      (node (ref "U18") (pin "2") (pinfunction "SDI_2") (pintype "passive"))
    )
    (net (code "58") (name "Net-(U18-R-EXT)") (class "Default")
      (node (ref "R47") (pin "2") (pinfunction "2_2") (pintype "passive"))
      (node (ref "U18") (pin "23") (pinfunction "R-EXT_23") (pintype "passive"))
    )
    (net (code "59") (name "Net-(U18-SDO)") (class "Default")
      (node (ref "U18") (pin "22") (pinfunction "SDO_22") (pintype "passive"))
      (node (ref "U19") (pin "2") (pinfunction "SDI_2") (pintype "passive"))
    )
    (net (code "60") (name "Net-(U19-R-EXT)") (class "Default")
      (node (ref "R48") (pin "2") (pinfunction "2_2") (pintype "passive"))
      (node (ref "U19") (pin "23") (pinfunction "R-EXT_23") (pintype "passive"))
    )
    (net (code "61") (name "Net-(U19-SDO)") (class "Default")
      (node (ref "U19") (pin "22") (pinfunction "SDO_22") (pintype "passive"))
      (node (ref "U20") (pin "2") (pinfunction "SDI_2") (pintype "passive"))
    )
    (net (code "62") (name "Net-(U20-R-EXT)") (class "Default")
      (node (ref "R49") (pin "2") (pinfunction "2_2") (pintype "passive"))
      (node (ref "U20") (pin "23") (pinfunction "R-EXT_23") (pintype "passive"))
    )
    (net (code "63") (name "Net-(U21-FB)") (class "Default")
      (node (ref "R52") (pin "1") (pinfunction "1_1") (pintype "passive"))
      (node (ref "R54") (pin "2") (pinfunction "2_2") (pintype "passive"))
      (node (ref "U21") (pin "3") (pinfunction "FB_3") (pintype "passive"))
    )
    (net (code "64") (name "Net-(U21-SW)") (class "Default")
      (node (ref "L8") (pin "2") (pinfunction "2_2") (pintype "passive"))
      (node (ref "U21") (pin "7") (pinfunction "SW_7") (pintype "passive"))
    )
    (net (code "65") (name "VLED") (class "Default")
      (node (ref "C88") (pin "1") (pinfunction "1_1") (pintype "passive"))
      (node (ref "C89") (pin "1") (pinfunction "1_1") (pintype "passive"))
      (node (ref "C91") (pin "1") (pinfunction "1_1") (pintype "passive"))
      (node (ref "C92") (pin "1") (pinfunction "1_1") (pintype "passive"))
      (node (ref "J10") (pin "41") (pinfunction "41_41") (pintype "passive"))
      (node (ref "J10") (pin "42") (pinfunction "42_42") (pintype "passive"))
      (node (ref "J10") (pin "43") (pinfunction "43_43") (pintype "passive"))
      (node (ref "J10") (pin "44") (pinfunction "44_44") (pintype "passive"))
      (node (ref "J10") (pin "45") (pinfunction "45_45") (pintype "passive"))
      (node (ref "L8") (pin "1") (pinfunction "1_1") (pintype "passive"))
      (node (ref "R52") (pin "2") (pinfunction "2_2") (pintype "passive"))
      (node (ref "TP44") (pin "1") (pinfunction "1_1") (pintype "passive"))
    )
    (net (code "66") (name "unconnected-(U20-SDO-Pad22)") (class "Default")
      (node (ref "U20") (pin "22") (pinfunction "SDO_22") (pintype "passive+no_connect"))
    )
    (net (code "67") (name "unconnected-(U21-PG-Pad5)") (class "Default")
      (node (ref "U21") (pin "5") (pinfunction "PG_5") (pintype "output+no_connect"))
    )
  )
)
